# Display_Interface.net
KiCad netlist of a schematic drawn in Altium Designer
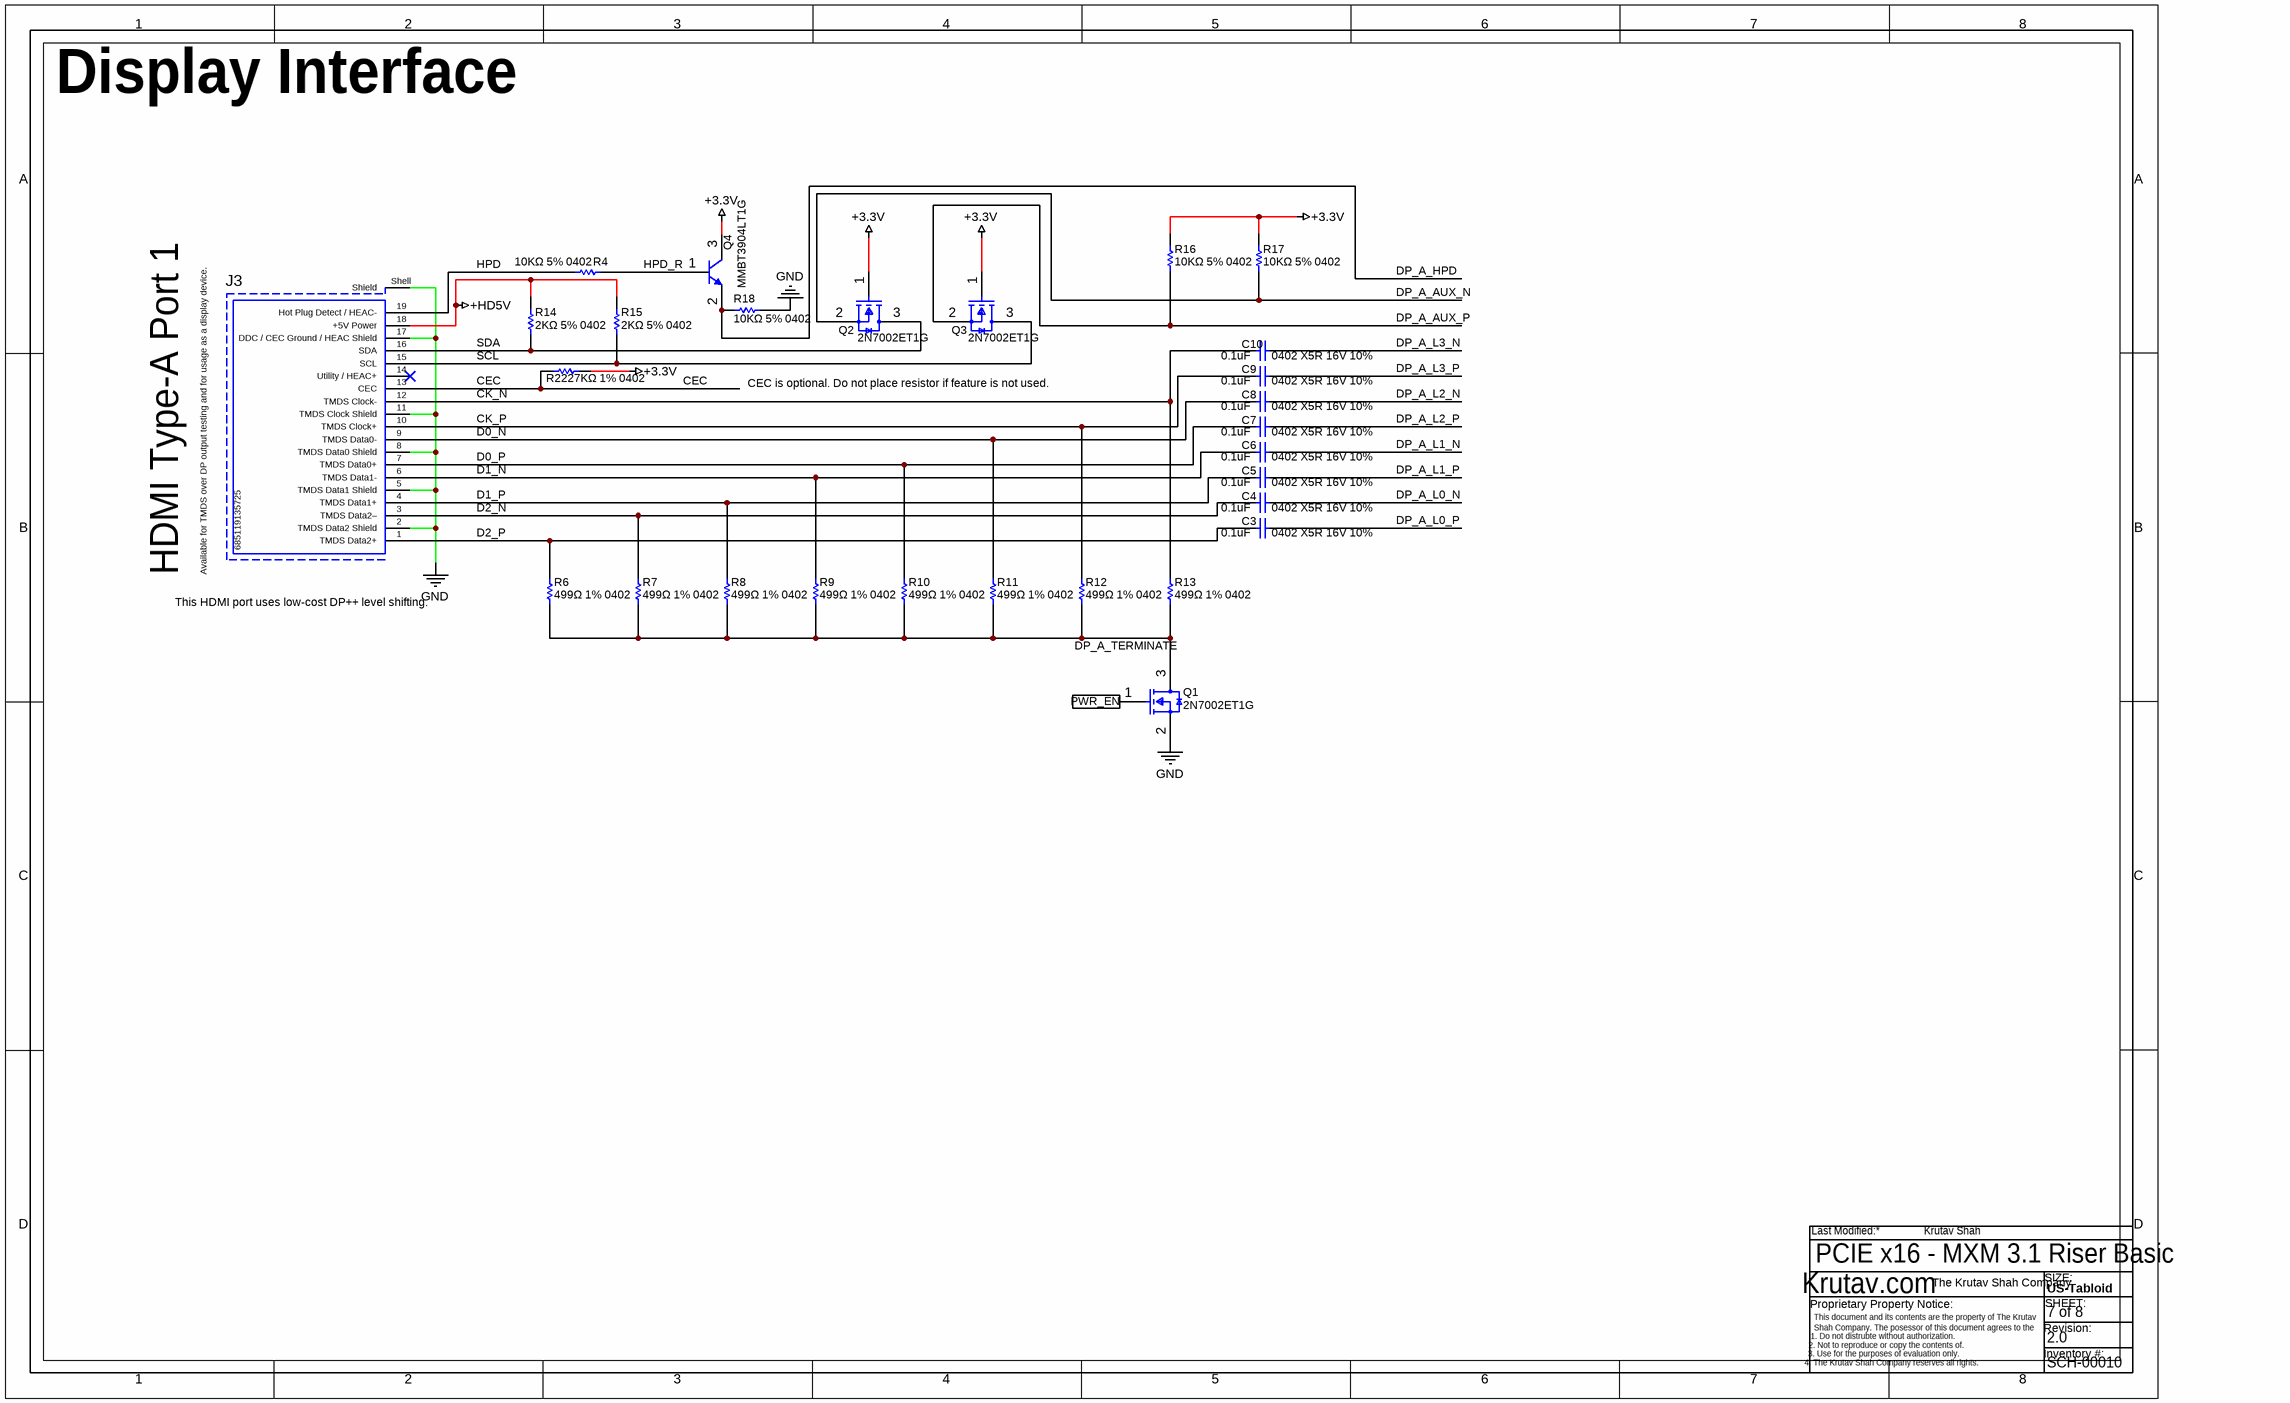
[diagram p0: Display Interface.SchDoc]

(export (version "E")
  (design (tool "Eeschema 10.0.6"))
  (components
    (comp (ref "C3")
      (value "0.1uF       0402 X5R 16V 10%")
      (footprint "CAPC0603X33X15NL03T05")
      (fields (field (name "MANUFACTURER") "Samsung") (field (name "PART NUMBER") "CL03A224MQ3NNNC"))
      (libsource (lib "Altium Content Vault") (part "CAP"))
    )
    (comp (ref "C4")
      (value "0.1uF       0402 X5R 16V 10%")
      (footprint "CAPC0603X33X15NL03T05")
      (fields (field (name "MANUFACTURER") "Samsung") (field (name "PART NUMBER") "CL03A224MQ3NNNC"))
      (libsource (lib "Altium Content Vault") (part "CAP"))
    )
    (comp (ref "C5")
      (value "0.1uF       0402 X5R 16V 10%")
      (footprint "CAPC0603X33X15NL03T05")
      (fields (field (name "MANUFACTURER") "Samsung") (field (name "PART NUMBER") "CL03A224MQ3NNNC"))
      (libsource (lib "Altium Content Vault") (part "CAP"))
    )
    (comp (ref "C6")
      (value "0.1uF       0402 X5R 16V 10%")
      (footprint "CAPC0603X33X15NL03T05")
      (fields (field (name "MANUFACTURER") "Samsung") (field (name "PART NUMBER") "CL03A224MQ3NNNC"))
      (libsource (lib "Altium Content Vault") (part "CAP"))
    )
    (comp (ref "C7")
      (value "0.1uF       0402 X5R 16V 10%")
      (footprint "CAPC0603X33X15NL03T05")
      (fields (field (name "MANUFACTURER") "Samsung") (field (name "PART NUMBER") "CL03A224MQ3NNNC"))
      (libsource (lib "Altium Content Vault") (part "CAP"))
    )
    (comp (ref "C8")
      (value "0.1uF       0402 X5R 16V 10%")
      (footprint "CAPC0603X33X15NL03T05")
      (fields (field (name "MANUFACTURER") "Samsung") (field (name "PART NUMBER") "CL03A224MQ3NNNC"))
      (libsource (lib "Altium Content Vault") (part "CAP"))
    )
    (comp (ref "C9")
      (value "0.1uF       0402 X5R 16V 10%")
      (footprint "CAPC0603X33X15NL03T05")
      (fields (field (name "MANUFACTURER") "Samsung") (field (name "PART NUMBER") "CL03A224MQ3NNNC"))
      (libsource (lib "Altium Content Vault") (part "CAP"))
    )
    (comp (ref "C10")
      (value "0.1uF       0402 X5R 16V 10%")
      (footprint "CAPC0603X33X15NL03T05")
      (fields (field (name "MANUFACTURER") "Samsung") (field (name "PART NUMBER") "CL03A224MQ3NNNC"))
      (libsource (lib "Altium Content Vault") (part "CAP"))
    )
    (comp (ref "J3")
      (value "685119135725")
      (footprint "685119135725")
      (description "HDMI Type A Receptacle WR-COM, Horizontal, SMT, with M3 Screw Flange")
      (fields (field (name "MANUFACTURER") "Wurth Elektronik") (field (name "PUBLISHER") "WurthElektronik"))
      (libsource (lib "Altium Content Vault") (part "WE-CN-1P-1F-HD19"))
    )
    (comp (ref "Q1")
      (value "2N7002ET1G")
      (footprint "FP-318-08-IPC_A")
      (description "MOSFET N-CH 60V 260MA SOT-23")
      (libsource (lib "Altium Content Vault") (part "a04dfd38ebfed9f67ad7f4c51a87371"))
    )
    (comp (ref "Q2")
      (value "2N7002ET1G")
      (footprint "FP-318-08-IPC_A")
      (description "MOSFET N-CH 60V 260MA SOT-23")
      (libsource (lib "Altium Content Vault") (part "a04dfd38ebfed9f67ad7f4c51a87371"))
    )
    (comp (ref "Q3")
      (value "2N7002ET1G")
      (footprint "FP-318-08-IPC_A")
      (description "MOSFET N-CH 60V 260MA SOT-23")
      (libsource (lib "Altium Content Vault") (part "a04dfd38ebfed9f67ad7f4c51a87371"))
    )
    (comp (ref "Q4")
      (value "MMBT3904LT1G")
      (footprint "ONSC-SOT-23-3-318-08_V")
      (description "General Purpose Transistor, NPN Silicon, 3-Pin SOT-23, Pb-Free, Tape and Reel")
      (fields (field (name "MANUFACTURER") "On Semiconductor"))
      (libsource (lib "Altium Content Vault") (part "ONSC-NPN-B1E2C3-3"))
    )
    (comp (ref "R4")
      (value "10KΩ 5% 0402")
      (footprint "RESC0201(0603)_L")
      (description "1M 0.05W 1% 0201 (0603 Metric)  SMD")
      (fields (field (name "TOLERANCE") "1 %") (field (name "POWER") "0.05 W"))
      (libsource (lib "Altium Content Vault") (part "RES"))
    )
    (comp (ref "R6")
      (value "499Ω 1% 0402")
      (footprint "RESC0201(0603)_L")
      (description "1M 0.05W 1% 0201 (0603 Metric)  SMD")
      (fields (field (name "TOLERANCE") "1 %") (field (name "POWER") "0.05 W"))
      (libsource (lib "Altium Content Vault") (part "RES"))
    )
    (comp (ref "R7")
      (value "499Ω 1% 0402")
      (footprint "RESC0201(0603)_L")
      (description "1M 0.05W 1% 0201 (0603 Metric)  SMD")
      (fields (field (name "TOLERANCE") "1 %") (field (name "POWER") "0.05 W"))
      (libsource (lib "Altium Content Vault") (part "RES"))
    )
    (comp (ref "R8")
      (value "499Ω 1% 0402")
      (footprint "RESC0201(0603)_L")
      (description "1M 0.05W 1% 0201 (0603 Metric)  SMD")
      (fields (field (name "TOLERANCE") "1 %") (field (name "POWER") "0.05 W"))
      (libsource (lib "Altium Content Vault") (part "RES"))
    )
    (comp (ref "R9")
      (value "499Ω 1% 0402")
      (footprint "RESC0201(0603)_L")
      (description "1M 0.05W 1% 0201 (0603 Metric)  SMD")
      (fields (field (name "TOLERANCE") "1 %") (field (name "POWER") "0.05 W"))
      (libsource (lib "Altium Content Vault") (part "RES"))
    )
    (comp (ref "R10")
      (value "499Ω 1% 0402")
      (footprint "RESC0201(0603)_L")
      (description "1M 0.05W 1% 0201 (0603 Metric)  SMD")
      (fields (field (name "TOLERANCE") "1 %") (field (name "POWER") "0.05 W"))
      (libsource (lib "Altium Content Vault") (part "RES"))
    )
    (comp (ref "R11")
      (value "499Ω 1% 0402")
      (footprint "RESC0201(0603)_L")
      (description "1M 0.05W 1% 0201 (0603 Metric)  SMD")
      (fields (field (name "TOLERANCE") "1 %") (field (name "POWER") "0.05 W"))
      (libsource (lib "Altium Content Vault") (part "RES"))
    )
    (comp (ref "R12")
      (value "499Ω 1% 0402")
      (footprint "RESC0201(0603)_L")
      (description "1M 0.05W 1% 0201 (0603 Metric)  SMD")
      (fields (field (name "TOLERANCE") "1 %") (field (name "POWER") "0.05 W"))
      (libsource (lib "Altium Content Vault") (part "RES"))
    )
    (comp (ref "R13")
      (value "499Ω 1% 0402")
      (footprint "RESC0201(0603)_L")
      (description "1M 0.05W 1% 0201 (0603 Metric)  SMD")
      (fields (field (name "TOLERANCE") "1 %") (field (name "POWER") "0.05 W"))
      (libsource (lib "Altium Content Vault") (part "RES"))
    )
    (comp (ref "R14")
      (value "2KΩ 5% 0402")
      (footprint "RESC0201(0603)_L")
      (description "1M 0.05W 1% 0201 (0603 Metric)  SMD")
      (fields (field (name "TOLERANCE") "1 %") (field (name "POWER") "0.05 W"))
      (libsource (lib "Altium Content Vault") (part "RES"))
    )
    (comp (ref "R15")
      (value "2KΩ 5% 0402")
      (footprint "RESC0201(0603)_L")
      (description "1M 0.05W 1% 0201 (0603 Metric)  SMD")
      (fields (field (name "TOLERANCE") "1 %") (field (name "POWER") "0.05 W"))
      (libsource (lib "Altium Content Vault") (part "RES"))
    )
    (comp (ref "R16")
      (value "10KΩ 5% 0402")
      (footprint "RESC0201(0603)_L")
      (description "1M 0.05W 1% 0201 (0603 Metric)  SMD")
      (fields (field (name "TOLERANCE") "1 %") (field (name "POWER") "0.05 W"))
      (libsource (lib "Altium Content Vault") (part "RES"))
    )
    (comp (ref "R17")
      (value "10KΩ 5% 0402")
      (footprint "RESC0201(0603)_L")
      (description "1M 0.05W 1% 0201 (0603 Metric)  SMD")
      (fields (field (name "TOLERANCE") "1 %") (field (name "POWER") "0.05 W"))
      (libsource (lib "Altium Content Vault") (part "RES"))
    )
    (comp (ref "R18")
      (value "10KΩ 5% 0402")
      (footprint "RESC0201(0603)_L")
      (description "1M 0.05W 1% 0201 (0603 Metric)  SMD")
      (fields (field (name "TOLERANCE") "1 %") (field (name "POWER") "0.05 W"))
      (libsource (lib "Altium Content Vault") (part "RES"))
    )
    (comp (ref "R22")
      (value "27KΩ 1% 0402")
      (footprint "RESC0201(0603)_L")
      (description "1M 0.05W 1% 0201 (0603 Metric)  SMD")
      (fields (field (name "TOLERANCE") "1 %") (field (name "POWER") "0.05 W"))
      (libsource (lib "Altium Content Vault") (part "RES"))
    )
  )
  (nets
    (net (code "1") (name "+3.3V") (class "Default")
      (node (ref "Q2") (pin "1") (pinfunction "Gate_1") (pintype "passive"))
      (node (ref "Q3") (pin "1") (pinfunction "Gate_1") (pintype "passive"))
      (node (ref "Q4") (pin "3") (pinfunction "C_3") (pintype "passive"))
      (node (ref "R16") (pin "1") (pinfunction "1_1") (pintype "passive"))
      (node (ref "R17") (pin "1") (pinfunction "1_1") (pintype "passive"))
      (node (ref "R22") (pin "1") (pinfunction "1_1") (pintype "passive"))
    )
    (net (code "2") (name "+HD5V") (class "Default")
      (node (ref "J3") (pin "18") (pinfunction "+5V_Power_18") (pintype "passive"))
      (node (ref "R14") (pin "1") (pinfunction "1_1") (pintype "passive"))
      (node (ref "R15") (pin "1") (pinfunction "1_1") (pintype "passive"))
    )
    (net (code "3") (name "/CEC") (class "Default")
      (node (ref "J3") (pin "13") (pinfunction "CEC_13") (pintype "passive"))
      (node (ref "R22") (pin "2") (pinfunction "2_2") (pintype "passive"))
    )
    (net (code "4") (name "/CK_N") (class "Default")
      (node (ref "C10") (pin "1") (pinfunction "1_1") (pintype "passive"))
      (node (ref "J3") (pin "12") (pinfunction "TMDS_Clock-_12") (pintype "passive"))
      (node (ref "R13") (pin "1") (pinfunction "1_1") (pintype "passive"))
    )
    (net (code "5") (name "/CK_P") (class "Default")
      (node (ref "C9") (pin "1") (pinfunction "1_1") (pintype "passive"))
      (node (ref "J3") (pin "10") (pinfunction "TMDS_Clock+_10") (pintype "passive"))
      (node (ref "R12") (pin "1") (pinfunction "1_1") (pintype "passive"))
    )
    (net (code "6") (name "/D0_N") (class "Default")
      (node (ref "C8") (pin "1") (pinfunction "1_1") (pintype "passive"))
      (node (ref "J3") (pin "9") (pinfunction "TMDS_Data0-_9") (pintype "passive"))
      (node (ref "R11") (pin "1") (pinfunction "1_1") (pintype "passive"))
    )
    (net (code "7") (name "/D0_P") (class "Default")
      (node (ref "C7") (pin "1") (pinfunction "1_1") (pintype "passive"))
      (node (ref "J3") (pin "7") (pinfunction "TMDS_Data0+_7") (pintype "passive"))
      (node (ref "R10") (pin "1") (pinfunction "1_1") (pintype "passive"))
    )
    (net (code "8") (name "/D1_N") (class "Default")
      (node (ref "C6") (pin "1") (pinfunction "1_1") (pintype "passive"))
      (node (ref "J3") (pin "6") (pinfunction "TMDS_Data1-_6") (pintype "passive"))
      (node (ref "R9") (pin "1") (pinfunction "1_1") (pintype "passive"))
    )
    (net (code "9") (name "/D1_P") (class "Default")
      (node (ref "C5") (pin "1") (pinfunction "1_1") (pintype "passive"))
      (node (ref "J3") (pin "4") (pinfunction "TMDS_Data1+_4") (pintype "passive"))
      (node (ref "R8") (pin "1") (pinfunction "1_1") (pintype "passive"))
    )
    (net (code "10") (name "/D2_N") (class "Default")
      (node (ref "C4") (pin "1") (pinfunction "1_1") (pintype "passive"))
      (node (ref "J3") (pin "3") (pinfunction "TMDS_Data2–_3") (pintype "passive"))
      (node (ref "R7") (pin "1") (pinfunction "1_1") (pintype "passive"))
    )
    (net (code "11") (name "/D2_P") (class "Default")
      (node (ref "C3") (pin "1") (pinfunction "1_1") (pintype "passive"))
      (node (ref "J3") (pin "1") (pinfunction "TMDS_Data2+_1") (pintype "passive"))
      (node (ref "R6") (pin "1") (pinfunction "1_1") (pintype "passive"))
    )
    (net (code "12") (name "/DP_A_AUX_N") (class "Default")
      (node (ref "Q2") (pin "2") (pinfunction "Source_2") (pintype "passive"))
      (node (ref "R17") (pin "2") (pinfunction "2_2") (pintype "passive"))
    )
    (net (code "13") (name "/DP_A_AUX_P") (class "Default")
      (node (ref "Q3") (pin "2") (pinfunction "Source_2") (pintype "passive"))
      (node (ref "R16") (pin "2") (pinfunction "2_2") (pintype "passive"))
    )
    (net (code "14") (name "/DP_A_HPD") (class "Default")
      (node (ref "Q4") (pin "2") (pinfunction "E_2") (pintype "passive"))
      (node (ref "R18") (pin "1") (pinfunction "1_1") (pintype "passive"))
    )
    (net (code "15") (name "/DP_A_L0_N") (class "Default")
      (node (ref "C4") (pin "2") (pinfunction "2_2") (pintype "passive"))
    )
    (net (code "16") (name "/DP_A_L0_P") (class "Default")
      (node (ref "C3") (pin "2") (pinfunction "2_2") (pintype "passive"))
    )
    (net (code "17") (name "/DP_A_L1_N") (class "Default")
      (node (ref "C6") (pin "2") (pinfunction "2_2") (pintype "passive"))
    )
    (net (code "18") (name "/DP_A_L1_P") (class "Default")
      (node (ref "C5") (pin "2") (pinfunction "2_2") (pintype "passive"))
    )
    (net (code "19") (name "/DP_A_L2_N") (class "Default")
      (node (ref "C8") (pin "2") (pinfunction "2_2") (pintype "passive"))
    )
    (net (code "20") (name "/DP_A_L2_P") (class "Default")
      (node (ref "C7") (pin "2") (pinfunction "2_2") (pintype "passive"))
    )
    (net (code "21") (name "/DP_A_L3_N") (class "Default")
      (node (ref "C10") (pin "2") (pinfunction "2_2") (pintype "passive"))
    )
    (net (code "22") (name "/DP_A_L3_P") (class "Default")
      (node (ref "C9") (pin "2") (pinfunction "2_2") (pintype "passive"))
    )
    (net (code "23") (name "/DP_A_TERMINATE") (class "Default")
      (node (ref "Q1") (pin "3") (pinfunction "Drain_3") (pintype "passive"))
      (node (ref "R10") (pin "2") (pinfunction "2_2") (pintype "passive"))
      (node (ref "R11") (pin "2") (pinfunction "2_2") (pintype "passive"))
      (node (ref "R12") (pin "2") (pinfunction "2_2") (pintype "passive"))
      (node (ref "R13") (pin "2") (pinfunction "2_2") (pintype "passive"))
      (node (ref "R6") (pin "2") (pinfunction "2_2") (pintype "passive"))
      (node (ref "R7") (pin "2") (pinfunction "2_2") (pintype "passive"))
      (node (ref "R8") (pin "2") (pinfunction "2_2") (pintype "passive"))
      (node (ref "R9") (pin "2") (pinfunction "2_2") (pintype "passive"))
    )
    (net (code "24") (name "/HPD") (class "Default")
      (node (ref "J3") (pin "19") (pinfunction "Hot_Plug_Detect_/_HEAC-_19") (pintype "passive"))
      (node (ref "R4") (pin "2") (pinfunction "2_2") (pintype "passive"))
    )
    (net (code "25") (name "/HPD_R") (class "Default")
      (node (ref "Q4") (pin "1") (pinfunction "B_1") (pintype "passive"))
      (node (ref "R4") (pin "1") (pinfunction "1_1") (pintype "passive"))
    )
    (net (code "26") (name "/PWR_EN") (class "Default")
      (node (ref "Q1") (pin "1") (pinfunction "Gate_1") (pintype "passive"))
    )
    (net (code "27") (name "/SCL") (class "Default")
      (node (ref "J3") (pin "15") (pinfunction "SCL_15") (pintype "passive"))
      (node (ref "Q3") (pin "3") (pinfunction "Drain_3") (pintype "passive"))
      (node (ref "R15") (pin "2") (pinfunction "2_2") (pintype "passive"))
    )
    (net (code "28") (name "/SDA") (class "Default")
      (node (ref "J3") (pin "16") (pinfunction "SDA_16") (pintype "passive"))
      (node (ref "Q2") (pin "3") (pinfunction "Drain_3") (pintype "passive"))
      (node (ref "R14") (pin "2") (pinfunction "2_2") (pintype "passive"))
    )
    (net (code "29") (name "GND") (class "Default")
      (node (ref "J3") (pin "11") (pinfunction "TMDS_Clock_Shield_11") (pintype "passive"))
      (node (ref "J3") (pin "17") (pinfunction "DDC_/_CEC_Ground_/_HEAC_Shield_17") (pintype "passive"))
      (node (ref "J3") (pin "2") (pinfunction "TMDS_Data2_Shield_2") (pintype "passive"))
      (node (ref "J3") (pin "5") (pinfunction "TMDS_Data1_Shield_5") (pintype "passive"))
      (node (ref "J3") (pin "8") (pinfunction "TMDS_Data0_Shield_8") (pintype "passive"))
      (node (ref "J3") (pin "Shell") (pinfunction "Shield_Shell") (pintype "passive"))
      (node (ref "Q1") (pin "2") (pinfunction "Source_2") (pintype "passive"))
      (node (ref "R18") (pin "2") (pinfunction "2_2") (pintype "passive"))
    )
    (net (code "30") (name "unconnected-(J3-Utility_{slash}_HEAC+-Pad14)") (class "Default")
      (node (ref "J3") (pin "14") (pinfunction "Utility_/_HEAC+_14") (pintype "passive+no_connect"))
    )
  )
)
